# SparkFun_ProMicro_RP2350.net
KiCad netlist of a schematic drawn in EAGLE
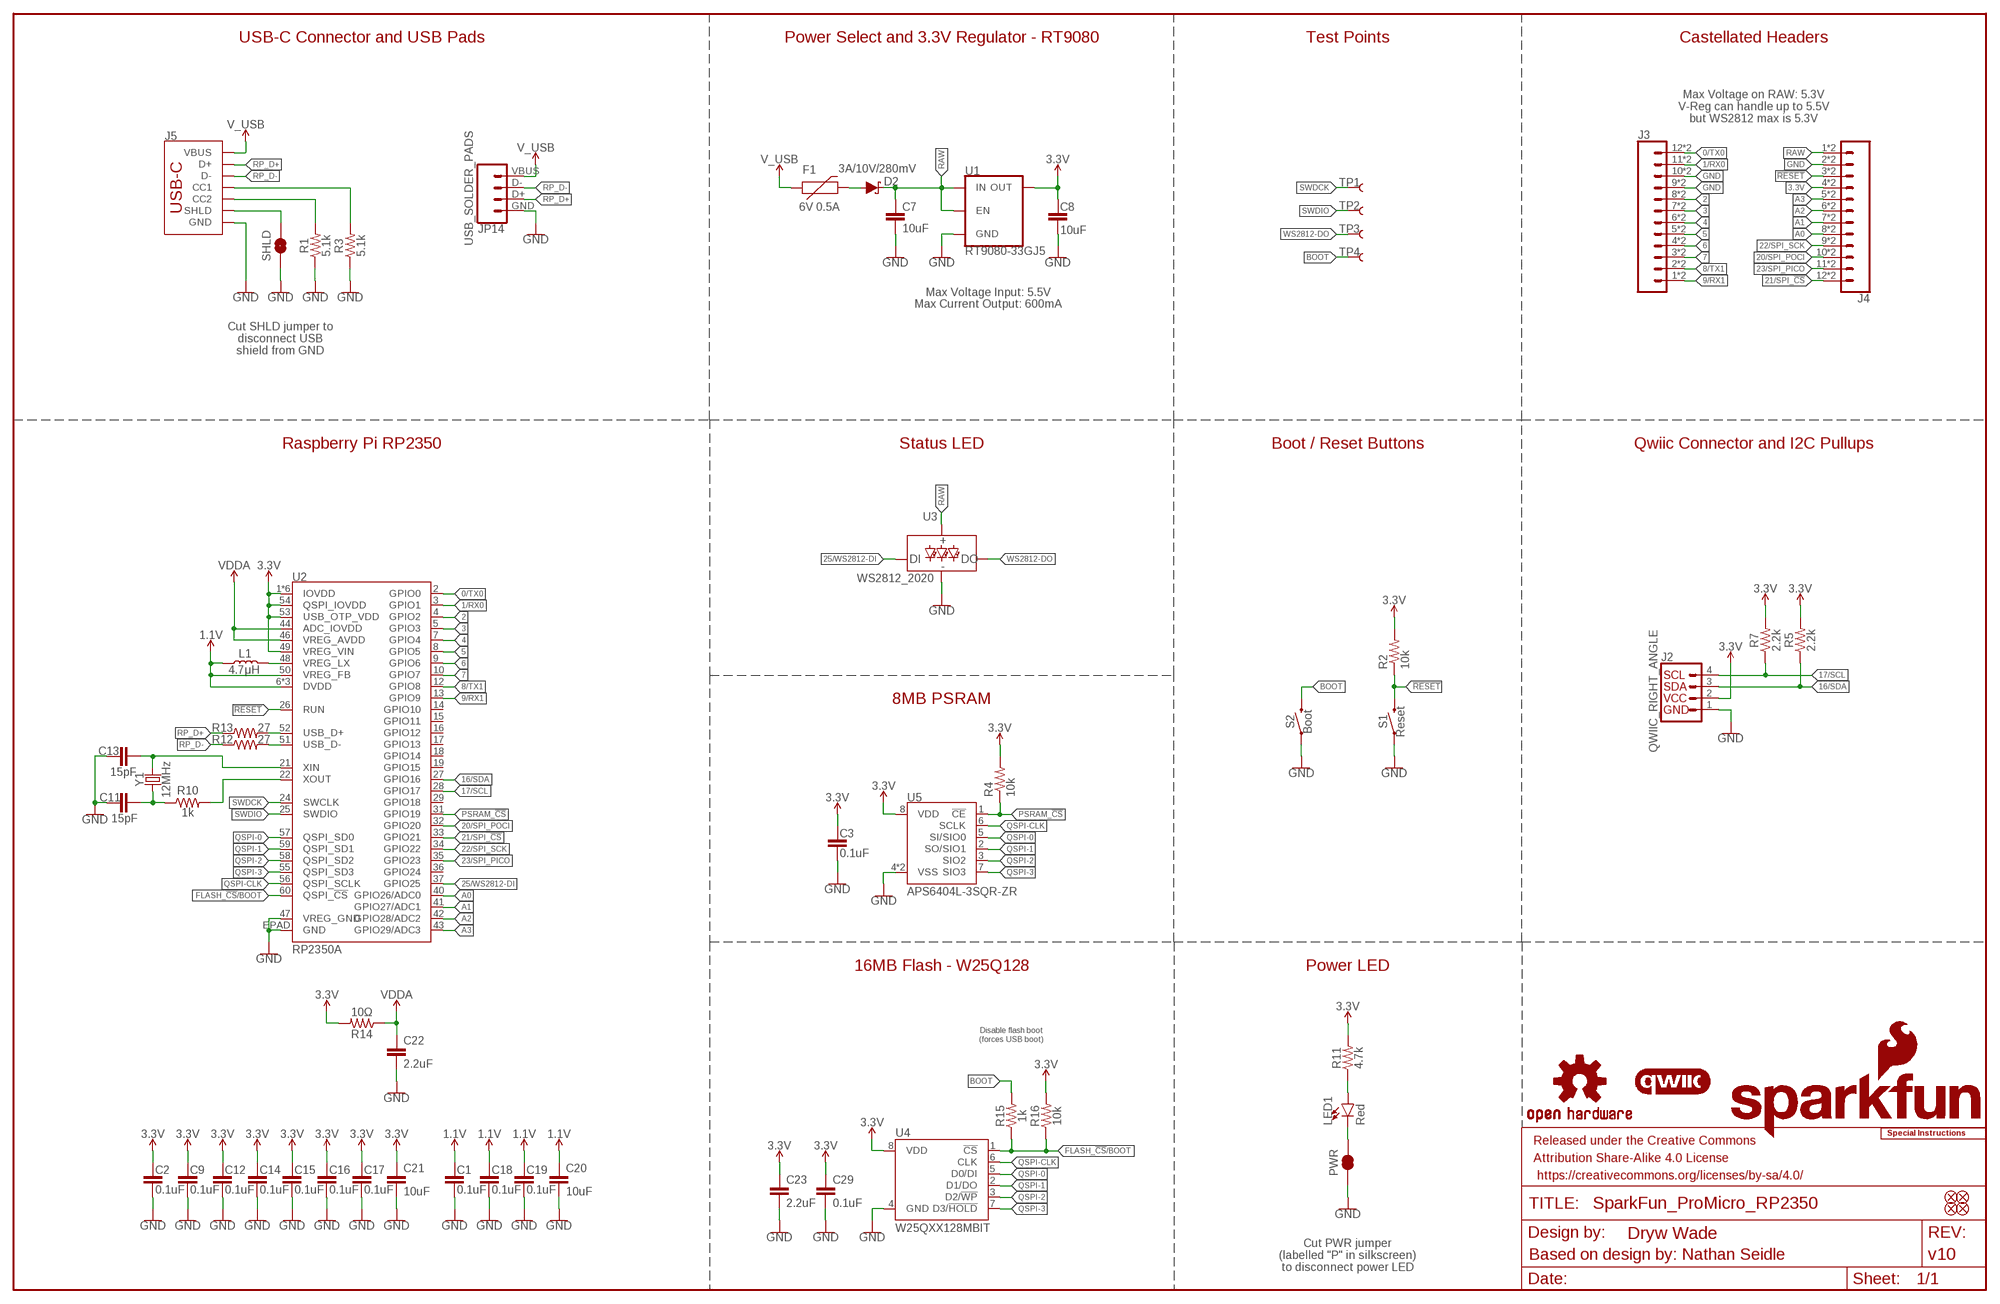
[diagram p0: schematic, sheet 1]

(export (version "E")
  (design (tool "Eeschema 10.0.6"))
  (components
    (comp (ref "C1")
      (value "0.1uF")
      (footprint "eagle-import:0402-TIGHT")
      (libsource (lib "eagle-import") (part "0.1UF-0402T-6.3V-10%-X7R"))
    )
    (comp (ref "C2")
      (value "0.1uF")
      (footprint "eagle-import:0402-TIGHT")
      (libsource (lib "eagle-import") (part "0.1UF-0402T-6.3V-10%-X7R"))
    )
    (comp (ref "C3")
      (value "0.1uF")
      (footprint "eagle-import:0402-TIGHT")
      (libsource (lib "eagle-import") (part "0.1UF-0402T-6.3V-10%-X7R"))
    )
    (comp (ref "C7")
      (value "10uF")
      (footprint "eagle-import:0402-TIGHT")
      (libsource (lib "eagle-import") (part "10UF-0402T-6.3V-20%"))
    )
    (comp (ref "C8")
      (value "10uF")
      (footprint "eagle-import:0402-TIGHT")
      (libsource (lib "eagle-import") (part "10UF-0402T-6.3V-20%"))
    )
    (comp (ref "C9")
      (value "0.1uF")
      (footprint "eagle-import:0402-TIGHT")
      (libsource (lib "eagle-import") (part "0.1UF-0402T-6.3V-10%-X7R"))
    )
    (comp (ref "C11")
      (value "15pF")
      (footprint "eagle-import:0402-TIGHT")
      (libsource (lib "eagle-import") (part "15PF-0402T-50V-5%"))
    )
    (comp (ref "C12")
      (value "0.1uF")
      (footprint "eagle-import:0402-TIGHT")
      (libsource (lib "eagle-import") (part "0.1UF-0402T-6.3V-10%-X7R"))
    )
    (comp (ref "C13")
      (value "15pF")
      (footprint "eagle-import:0402-TIGHT")
      (libsource (lib "eagle-import") (part "15PF-0402T-50V-5%"))
    )
    (comp (ref "C14")
      (value "0.1uF")
      (footprint "eagle-import:0402-TIGHT")
      (libsource (lib "eagle-import") (part "0.1UF-0402T-6.3V-10%-X7R"))
    )
    (comp (ref "C15")
      (value "0.1uF")
      (footprint "eagle-import:0402-TIGHT")
      (libsource (lib "eagle-import") (part "0.1UF-0402T-6.3V-10%-X7R"))
    )
    (comp (ref "C16")
      (value "0.1uF")
      (footprint "eagle-import:0402-TIGHT")
      (libsource (lib "eagle-import") (part "0.1UF-0402T-6.3V-10%-X7R"))
    )
    (comp (ref "C17")
      (value "0.1uF")
      (footprint "eagle-import:0402-TIGHT")
      (libsource (lib "eagle-import") (part "0.1UF-0402T-6.3V-10%-X7R"))
    )
    (comp (ref "C18")
      (value "0.1uF")
      (footprint "eagle-import:0402-TIGHT")
      (libsource (lib "eagle-import") (part "0.1UF-0402T-6.3V-10%-X7R"))
    )
    (comp (ref "C19")
      (value "0.1uF")
      (footprint "eagle-import:0402-TIGHT")
      (libsource (lib "eagle-import") (part "0.1UF-0402T-6.3V-10%-X7R"))
    )
    (comp (ref "C20")
      (value "10uF")
      (footprint "eagle-import:0402-TIGHT")
      (libsource (lib "eagle-import") (part "10UF-0402T-6.3V-20%"))
    )
    (comp (ref "C21")
      (value "10uF")
      (footprint "eagle-import:0402-TIGHT")
      (libsource (lib "eagle-import") (part "10UF-0402T-6.3V-20%"))
    )
    (comp (ref "C22")
      (value "2.2uF")
      (footprint "eagle-import:0402-TIGHT")
      (libsource (lib "eagle-import") (part "2.2UF-0402_TIGHT-10V-10%-X5R"))
    )
    (comp (ref "C23")
      (value "2.2uF")
      (footprint "eagle-import:0402-TIGHT")
      (libsource (lib "eagle-import") (part "2.2UF-0402_TIGHT-10V-10%-X5R"))
    )
    (comp (ref "C29")
      (value "0.1uF")
      (footprint "eagle-import:0402-TIGHT")
      (libsource (lib "eagle-import") (part "0.1UF-0402T-6.3V-10%-X7R"))
    )
    (comp (ref "D2")
      (value "3A/10V/280mV")
      (footprint "eagle-import:SOD-323")
      (libsource (lib "eagle-import") (part "DIODE-SCHOTTKY-BAT60A"))
    )
    (comp (ref "F1")
      (value "6V 0.5A")
      (footprint "eagle-import:0805")
      (libsource (lib "eagle-import") (part "PPTC_6V500MA"))
    )
    (comp (ref "FRAME2")
      (value "FRAME-LEDGER")
      (footprint "eagle-import:CREATIVE_COMMONS")
      (fields (field (name "DESIGNER") "Dryw Wade") (field (name "REV") "v10"))
      (libsource (lib "eagle-import") (part "FRAME-LEDGER"))
    )
    (comp (ref "J2")
      (value "QWIIC_RIGHT_ANGLE")
      (footprint "eagle-import:JST04_1MM_RA")
      (libsource (lib "eagle-import") (part "QWIIC_CONNECTORJS-1MM"))
    )
    (comp (ref "J3")
      (value "CONN_12CASTELLATED")
      (footprint "eagle-import:1X12_CASTELLATED")
      (libsource (lib "eagle-import") (part "CONN_12CASTELLATED"))
    )
    (comp (ref "J4")
      (value "CONN_12CASTELLATED")
      (footprint "eagle-import:1X12_CASTELLATED")
      (libsource (lib "eagle-import") (part "CONN_12CASTELLATED"))
    )
    (comp (ref "J5")
      (value "USB Female Type C Connector")
      (footprint "eagle-import:USB-C-16P_4LAYER-PADS")
      (libsource (lib "eagle-import") (part "USB_C_4-LAYER_PADS"))
    )
    (comp (ref "JP1")
      (value "FIDUCIAL1X2")
      (footprint "eagle-import:FIDUCIAL-1X2")
      (libsource (lib "eagle-import") (part "FIDUCIAL1X2"))
    )
    (comp (ref "JP2")
      (value "FIDUCIAL1X2")
      (footprint "eagle-import:FIDUCIAL-1X2")
      (libsource (lib "eagle-import") (part "FIDUCIAL1X2"))
    )
    (comp (ref "JP3")
      (value "FIDUCIAL1X2")
      (footprint "eagle-import:FIDUCIAL-1X2")
      (libsource (lib "eagle-import") (part "FIDUCIAL1X2"))
    )
    (comp (ref "JP4")
      (value "FIDUCIAL1X2")
      (footprint "eagle-import:FIDUCIAL-1X2")
      (libsource (lib "eagle-import") (part "FIDUCIAL1X2"))
    )
    (comp (ref "JP14")
      (value "USB_SOLDER_PADS")
      (footprint "eagle-import:USB-SOLDER-PADS")
      (libsource (lib "eagle-import") (part "USB_SOLDER_PADS"))
    )
    (comp (ref "L1")
      (value "4.7μH")
      (footprint "eagle-import:1008(2520)")
      (libsource (lib "eagle-import") (part "4.7μH_SHIELDED_INDUCTOR"))
    )
    (comp (ref "LED1")
      (value "Red")
      (footprint "eagle-import:LED-0603")
      (libsource (lib "eagle-import") (part "LED-RED_0603-KB"))
    )
    (comp (ref "LOGO1")
      (value "SFE_LOGO_NAME_FLAME.1_INCH")
      (footprint "eagle-import:SFE_LOGO_NAME_FLAME_.1")
      (libsource (lib "eagle-import") (part "SFE_LOGO_NAME_FLAME.1_INCH"))
    )
    (comp (ref "LOGO3")
      (value "QWIIC_LOGO_6MM")
      (footprint "eagle-import:QWIIC_6MM")
      (libsource (lib "eagle-import") (part "QWIIC_LOGO_6MM"))
    )
    (comp (ref "LOGO4")
      (value "SFE_LOGO_FLAME.1_INCH")
      (footprint "eagle-import:SFE_LOGO_FLAME_.1")
      (libsource (lib "eagle-import") (part "SFE_LOGO_FLAME.1_INCH"))
    )
    (comp (ref "LOGO5")
      (value "SPECIAL_INSTRUCTIONS-ORDERING")
      (footprint "eagle-import:ORDERING_INSTRUCTIONS")
      (libsource (lib "eagle-import") (part "SPECIAL_INSTRUCTIONS-ORDERING"))
    )
    (comp (ref "PWR")
      (value "JUMPER-SMT_2_NC_TRACE_SILK")
      (footprint "eagle-import:SMT-JUMPER_2_NC_TRACE_SILK")
      (libsource (lib "eagle-import") (part "JUMPER-SMT_2_NC_TRACE_SILK"))
    )
    (comp (ref "R1")
      (value "5.1k")
      (footprint "eagle-import:0402-TIGHT")
      (libsource (lib "eagle-import") (part "5.1KOHM-0402T-1/16W-1%"))
    )
    (comp (ref "R2")
      (value "10k")
      (footprint "eagle-import:0402-TIGHT")
      (libsource (lib "eagle-import") (part "10KOHM-0402T-1/16W-1%"))
    )
    (comp (ref "R3")
      (value "5.1k")
      (footprint "eagle-import:0402-TIGHT")
      (libsource (lib "eagle-import") (part "5.1KOHM-0402T-1/16W-1%"))
    )
    (comp (ref "R4")
      (value "10k")
      (footprint "eagle-import:0402-TIGHT")
      (libsource (lib "eagle-import") (part "10KOHM-0402T-1/16W-1%"))
    )
    (comp (ref "R5")
      (value "2.2k")
      (footprint "eagle-import:0402-TIGHT")
      (libsource (lib "eagle-import") (part "2.2KOHM-0402T-1/16W-1%"))
    )
    (comp (ref "R7")
      (value "2.2k")
      (footprint "eagle-import:0402-TIGHT")
      (libsource (lib "eagle-import") (part "2.2KOHM-0402T-1/16W-1%"))
    )
    (comp (ref "R10")
      (value "1k")
      (footprint "eagle-import:0402-TIGHT")
      (libsource (lib "eagle-import") (part "1KOHM-0402T-1/16W-1%"))
    )
    (comp (ref "R11")
      (value "4.7k")
      (footprint "eagle-import:0402-TIGHT")
      (libsource (lib "eagle-import") (part "4.7KOHM-0402T-1/16W-1%"))
    )
    (comp (ref "R12")
      (value "27")
      (footprint "eagle-import:0402-TIGHT")
      (libsource (lib "eagle-import") (part "27OHM"))
    )
    (comp (ref "R13")
      (value "27")
      (footprint "eagle-import:0402-TIGHT")
      (libsource (lib "eagle-import") (part "27OHM"))
    )
    (comp (ref "R14")
      (value "10Ω")
      (footprint "eagle-import:0402-TIGHT")
      (libsource (lib "eagle-import") (part "10OHM-0402-1/16W-5%"))
    )
    (comp (ref "R15")
      (value "1k")
      (footprint "eagle-import:0402-TIGHT")
      (libsource (lib "eagle-import") (part "1KOHM-0402T-1/16W-1%"))
    )
    (comp (ref "R16")
      (value "10k")
      (footprint "eagle-import:0402-TIGHT")
      (libsource (lib "eagle-import") (part "10KOHM-0402T-1/16W-1%"))
    )
    (comp (ref "S1")
      (value "Reset")
      (footprint "eagle-import:TACTILE_SWITCH_SMD_4.6X2.8MM")
      (libsource (lib "eagle-import") (part "MOMENTARY-SWITCH-SPST-SMD-4.6X2.8MM"))
    )
    (comp (ref "S2")
      (value "Boot")
      (footprint "eagle-import:TACTILE_SWITCH_SMD_4.6X2.8MM")
      (libsource (lib "eagle-import") (part "MOMENTARY-SWITCH-SPST-SMD-4.6X2.8MM"))
    )
    (comp (ref "SHLD")
      (value "JUMPER-SMT_2_NC_TRACE_SILK")
      (footprint "eagle-import:SMT-JUMPER_2_NC_TRACE_SILK")
      (libsource (lib "eagle-import") (part "JUMPER-SMT_2_NC_TRACE_SILK"))
    )
    (comp (ref "TP1")
      (value "TEST-POINT3X5")
      (footprint "eagle-import:PAD.03X.05")
      (libsource (lib "eagle-import") (part "TEST-POINT3X5"))
    )
    (comp (ref "TP2")
      (value "TEST-POINT3X5")
      (footprint "eagle-import:PAD.03X.05")
      (libsource (lib "eagle-import") (part "TEST-POINT3X5"))
    )
    (comp (ref "TP3")
      (value "TEST-POINT3X5")
      (footprint "eagle-import:PAD.03X.05")
      (libsource (lib "eagle-import") (part "TEST-POINT3X5"))
    )
    (comp (ref "TP4")
      (value "TEST-POINT3X5")
      (footprint "eagle-import:PAD.03X.05")
      (libsource (lib "eagle-import") (part "TEST-POINT3X5"))
    )
    (comp (ref "U$3")
      (value "OSHW-LOGOMINI")
      (footprint "eagle-import:OSHW-LOGO-MINI")
      (libsource (lib "eagle-import") (part "OSHW-LOGOMINI"))
    )
    (comp (ref "U1")
      (value "RT9080-33GJ5")
      (footprint "eagle-import:SOT23-5")
      (libsource (lib "eagle-import") (part "V_REG_RT9080-33GJ5"))
    )
    (comp (ref "U2")
      (value "RP2350A")
      (footprint "eagle-import:RP2350A")
      (libsource (lib "eagle-import") (part "RP2350A"))
    )
    (comp (ref "U3")
      (value "WS2812_2020")
      (footprint "eagle-import:WS2812-2020")
      (libsource (lib "eagle-import") (part "WS2812_2020"))
    )
    (comp (ref "U4")
      (value "W25QXX128MBIT")
      (footprint "eagle-import:WSON-8-6X5-SKINNY_CENTERPAD")
      (libsource (lib "eagle-import") (part "W25QXX128MBIT-6X5-SKINNY_CENTER"))
    )
    (comp (ref "U5")
      (value "APS6404L-3SQR-ZR")
      (footprint "eagle-import:APS6404L-3SQR-ZR")
      (libsource (lib "eagle-import") (part "APS6404L-3SQR-ZR"))
    )
    (comp (ref "Y1")
      (value "12MHz")
      (footprint "eagle-import:CRYSTAL-SMD-2X2.5MM")
      (libsource (lib "eagle-import") (part "CRYSTAL-12MHZ"))
    )
  )
  (nets
    (net (code "1") (name "/21{slash}SPI_~{CS}") (class "Default")
      (node (ref "J4") (pin "12") (pinfunction "12_12") (pintype "passive"))
      (node (ref "J4") (pin "12B") (pinfunction "12_12B") (pintype "passive"))
      (node (ref "U2") (pin "33") (pinfunction "GPIO21_33") (pintype "bidirectional"))
    )
    (net (code "2") (name "/FLASH_~{CS}{slash}BOOT") (class "Default")
      (node (ref "R15") (pin "1") (pinfunction "1_1") (pintype "passive"))
      (node (ref "R16") (pin "1") (pinfunction "1_1") (pintype "passive"))
      (node (ref "U2") (pin "60") (pinfunction "QSPI_~{CS}_60") (pintype "bidirectional"))
      (node (ref "U4") (pin "1") (pinfunction "~{CS}_1") (pintype "bidirectional"))
    )
    (net (code "3") (name "/PSRAM_~{CS}") (class "Default")
      (node (ref "R4") (pin "1") (pinfunction "1_1") (pintype "passive"))
      (node (ref "U2") (pin "31") (pinfunction "GPIO19_31") (pintype "bidirectional"))
      (node (ref "U5") (pin "1") (pinfunction "~{CE}_1") (pintype "bidirectional"))
    )
    (net (code "4") (name "/~{RESET}") (class "Default")
      (node (ref "J4") (pin "3") (pinfunction "3_3") (pintype "passive"))
      (node (ref "J4") (pin "3B") (pinfunction "3_3B") (pintype "passive"))
      (node (ref "R2") (pin "1") (pinfunction "1_1") (pintype "passive"))
      (node (ref "S1") (pin "3") (pinfunction "2_3") (pintype "passive"))
      (node (ref "S1") (pin "4") (pinfunction "2_4") (pintype "passive"))
      (node (ref "U2") (pin "26") (pinfunction "RUN_26") (pintype "bidirectional"))
    )
    (net (code "5") (name "0{slash}TX0") (class "Default")
      (node (ref "J3") (pin "12") (pinfunction "12_12") (pintype "passive"))
      (node (ref "J3") (pin "12B") (pinfunction "12_12B") (pintype "passive"))
      (node (ref "U2") (pin "2") (pinfunction "GPIO0_2") (pintype "bidirectional"))
    )
    (net (code "6") (name "1.1V") (class "Default")
      (node (ref "C1") (pin "1") (pinfunction "1_1") (pintype "passive"))
      (node (ref "C18") (pin "1") (pinfunction "1_1") (pintype "passive"))
      (node (ref "C19") (pin "1") (pinfunction "1_1") (pintype "passive"))
      (node (ref "C20") (pin "1") (pinfunction "1_1") (pintype "passive"))
      (node (ref "L1") (pin "1") (pinfunction "1_1") (pintype "passive"))
      (node (ref "U2") (pin "23") (pinfunction "DVDD_23") (pintype "bidirectional"))
      (node (ref "U2") (pin "39") (pinfunction "DVDD_39") (pintype "bidirectional"))
      (node (ref "U2") (pin "50") (pinfunction "VREG_FB_50") (pintype "bidirectional"))
      (node (ref "U2") (pin "6") (pinfunction "DVDD_6") (pintype "bidirectional"))
    )
    (net (code "7") (name "1{slash}RX0") (class "Default")
      (node (ref "J3") (pin "11") (pinfunction "11_11") (pintype "passive"))
      (node (ref "J3") (pin "11B") (pinfunction "11_11B") (pintype "passive"))
      (node (ref "U2") (pin "3") (pinfunction "GPIO1_3") (pintype "bidirectional"))
    )
    (net (code "8") (name "2") (class "Default")
      (node (ref "J3") (pin "8") (pinfunction "8_8") (pintype "passive"))
      (node (ref "J3") (pin "8B") (pinfunction "8_8B") (pintype "passive"))
      (node (ref "U2") (pin "4") (pinfunction "GPIO2_4") (pintype "bidirectional"))
    )
    (net (code "9") (name "3") (class "Default")
      (node (ref "J3") (pin "7") (pinfunction "7_7") (pintype "passive"))
      (node (ref "J3") (pin "7B") (pinfunction "7_7B") (pintype "passive"))
      (node (ref "U2") (pin "5") (pinfunction "GPIO3_5") (pintype "bidirectional"))
    )
    (net (code "10") (name "3.3V") (class "Default")
      (node (ref "C12") (pin "1") (pinfunction "1_1") (pintype "passive"))
      (node (ref "C14") (pin "1") (pinfunction "1_1") (pintype "passive"))
      (node (ref "C15") (pin "1") (pinfunction "1_1") (pintype "passive"))
      (node (ref "C16") (pin "1") (pinfunction "1_1") (pintype "passive"))
      (node (ref "C17") (pin "1") (pinfunction "1_1") (pintype "passive"))
      (node (ref "C2") (pin "1") (pinfunction "1_1") (pintype "passive"))
      (node (ref "C21") (pin "1") (pinfunction "1_1") (pintype "passive"))
      (node (ref "C23") (pin "1") (pinfunction "1_1") (pintype "passive"))
      (node (ref "C29") (pin "1") (pinfunction "1_1") (pintype "passive"))
      (node (ref "C3") (pin "1") (pinfunction "1_1") (pintype "passive"))
      (node (ref "C8") (pin "2") (pinfunction "2_2") (pintype "passive"))
      (node (ref "C9") (pin "1") (pinfunction "1_1") (pintype "passive"))
      (node (ref "J2") (pin "2") (pinfunction "2_2") (pintype "power_in"))
      (node (ref "J4") (pin "4") (pinfunction "4_4") (pintype "passive"))
      (node (ref "J4") (pin "4B") (pinfunction "4_4B") (pintype "passive"))
      (node (ref "R11") (pin "2") (pinfunction "2_2") (pintype "passive"))
      (node (ref "R14") (pin "2") (pinfunction "2_2") (pintype "passive"))
      (node (ref "R16") (pin "2") (pinfunction "2_2") (pintype "passive"))
      (node (ref "R2") (pin "2") (pinfunction "2_2") (pintype "passive"))
      (node (ref "R4") (pin "2") (pinfunction "2_2") (pintype "passive"))
      (node (ref "R5") (pin "2") (pinfunction "2_2") (pintype "passive"))
      (node (ref "R7") (pin "2") (pinfunction "2_2") (pintype "passive"))
      (node (ref "U1") (pin "5") (pinfunction "OUT_5") (pintype "passive"))
      (node (ref "U2") (pin "1") (pinfunction "IOVDD_1") (pintype "bidirectional"))
      (node (ref "U2") (pin "11") (pinfunction "IOVDD_11") (pintype "bidirectional"))
      (node (ref "U2") (pin "20") (pinfunction "IOVDD_20") (pintype "bidirectional"))
      (node (ref "U2") (pin "30") (pinfunction "IOVDD_30") (pintype "bidirectional"))
      (node (ref "U2") (pin "38") (pinfunction "IOVDD_38") (pintype "bidirectional"))
      (node (ref "U2") (pin "45") (pinfunction "IOVDD_45") (pintype "bidirectional"))
      (node (ref "U2") (pin "49") (pinfunction "VREG_VIN_49") (pintype "bidirectional"))
      (node (ref "U2") (pin "53") (pinfunction "USB_OTP_VDD_53") (pintype "bidirectional"))
      (node (ref "U2") (pin "54") (pinfunction "QSPI_IOVDD_54") (pintype "bidirectional"))
      (node (ref "U4") (pin "8") (pinfunction "VDD_8") (pintype "bidirectional"))
      (node (ref "U5") (pin "8") (pinfunction "VDD_8") (pintype "bidirectional"))
    )
    (net (code "11") (name "4") (class "Default")
      (node (ref "J3") (pin "6") (pinfunction "6_6") (pintype "passive"))
      (node (ref "J3") (pin "6B") (pinfunction "6_6B") (pintype "passive"))
      (node (ref "U2") (pin "7") (pinfunction "GPIO4_7") (pintype "bidirectional"))
    )
    (net (code "12") (name "5") (class "Default")
      (node (ref "J3") (pin "5") (pinfunction "5_5") (pintype "passive"))
      (node (ref "J3") (pin "5B") (pinfunction "5_5B") (pintype "passive"))
      (node (ref "U2") (pin "8") (pinfunction "GPIO5_8") (pintype "bidirectional"))
    )
    (net (code "13") (name "6") (class "Default")
      (node (ref "J3") (pin "4") (pinfunction "4_4") (pintype "passive"))
      (node (ref "J3") (pin "4B") (pinfunction "4_4B") (pintype "passive"))
      (node (ref "U2") (pin "9") (pinfunction "GPIO6_9") (pintype "bidirectional"))
    )
    (net (code "14") (name "7") (class "Default")
      (node (ref "J3") (pin "3") (pinfunction "3_3") (pintype "passive"))
      (node (ref "J3") (pin "3B") (pinfunction "3_3B") (pintype "passive"))
      (node (ref "U2") (pin "10") (pinfunction "GPIO7_10") (pintype "bidirectional"))
    )
    (net (code "15") (name "8{slash}TX1") (class "Default")
      (node (ref "J3") (pin "2") (pinfunction "2_2") (pintype "passive"))
      (node (ref "J3") (pin "2B") (pinfunction "2_2B") (pintype "passive"))
      (node (ref "U2") (pin "12") (pinfunction "GPIO8_12") (pintype "bidirectional"))
    )
    (net (code "16") (name "9{slash}RX1") (class "Default")
      (node (ref "J3") (pin "1") (pinfunction "1_1") (pintype "passive"))
      (node (ref "J3") (pin "1B") (pinfunction "1_1B") (pintype "passive"))
      (node (ref "U2") (pin "13") (pinfunction "GPIO9_13") (pintype "bidirectional"))
    )
    (net (code "17") (name "16{slash}SDA") (class "Default")
      (node (ref "J2") (pin "3") (pinfunction "3_3") (pintype "passive"))
      (node (ref "R5") (pin "1") (pinfunction "1_1") (pintype "passive"))
      (node (ref "U2") (pin "27") (pinfunction "GPIO16_27") (pintype "bidirectional"))
    )
    (net (code "18") (name "17{slash}SCL") (class "Default")
      (node (ref "J2") (pin "4") (pinfunction "4_4") (pintype "passive"))
      (node (ref "R7") (pin "1") (pinfunction "1_1") (pintype "passive"))
      (node (ref "U2") (pin "28") (pinfunction "GPIO17_28") (pintype "bidirectional"))
    )
    (net (code "19") (name "20{slash}SPI_POCI") (class "Default")
      (node (ref "J4") (pin "10") (pinfunction "10_10") (pintype "passive"))
      (node (ref "J4") (pin "10B") (pinfunction "10_10B") (pintype "passive"))
      (node (ref "U2") (pin "32") (pinfunction "GPIO20_32") (pintype "bidirectional"))
    )
    (net (code "20") (name "22{slash}SPI_SCK") (class "Default")
      (node (ref "J4") (pin "9") (pinfunction "9_9") (pintype "passive"))
      (node (ref "J4") (pin "9B") (pinfunction "9_9B") (pintype "passive"))
      (node (ref "U2") (pin "34") (pinfunction "GPIO22_34") (pintype "bidirectional"))
    )
    (net (code "21") (name "23{slash}SPI_PICO") (class "Default")
      (node (ref "J4") (pin "11") (pinfunction "11_11") (pintype "passive"))
      (node (ref "J4") (pin "11B") (pinfunction "11_11B") (pintype "passive"))
      (node (ref "U2") (pin "35") (pinfunction "GPIO23_35") (pintype "bidirectional"))
    )
    (net (code "22") (name "25{slash}WS2812-DI") (class "Default")
      (node (ref "U2") (pin "37") (pinfunction "GPIO25_37") (pintype "bidirectional"))
      (node (ref "U3") (pin "DI") (pinfunction "DI_DI") (pintype "bidirectional"))
    )
    (net (code "23") (name "A0") (class "Default")
      (node (ref "J4") (pin "8") (pinfunction "8_8") (pintype "passive"))
      (node (ref "J4") (pin "8B") (pinfunction "8_8B") (pintype "passive"))
      (node (ref "U2") (pin "40") (pinfunction "GPIO26/ADC0_40") (pintype "bidirectional"))
    )
    (net (code "24") (name "A1") (class "Default")
      (node (ref "J4") (pin "7") (pinfunction "7_7") (pintype "passive"))
      (node (ref "J4") (pin "7B") (pinfunction "7_7B") (pintype "passive"))
      (node (ref "U2") (pin "41") (pinfunction "GPIO27/ADC1_41") (pintype "bidirectional"))
    )
    (net (code "25") (name "A2") (class "Default")
      (node (ref "J4") (pin "6") (pinfunction "6_6") (pintype "passive"))
      (node (ref "J4") (pin "6B") (pinfunction "6_6B") (pintype "passive"))
      (node (ref "U2") (pin "42") (pinfunction "GPIO28/ADC2_42") (pintype "bidirectional"))
    )
    (net (code "26") (name "A3") (class "Default")
      (node (ref "J4") (pin "5") (pinfunction "5_5") (pintype "passive"))
      (node (ref "J4") (pin "5B") (pinfunction "5_5B") (pintype "passive"))
      (node (ref "U2") (pin "43") (pinfunction "GPIO29/ADC3_43") (pintype "bidirectional"))
    )
    (net (code "27") (name "BOOT") (class "Default")
      (node (ref "R15") (pin "2") (pinfunction "2_2") (pintype "passive"))
      (node (ref "S2") (pin "3") (pinfunction "2_3") (pintype "passive"))
      (node (ref "S2") (pin "4") (pinfunction "2_4") (pintype "passive"))
      (node (ref "TP4") (pin "1") (pinfunction "1_1") (pintype "bidirectional"))
    )
    (net (code "28") (name "GND") (class "Default")
      (node (ref "C1") (pin "2") (pinfunction "2_2") (pintype "passive"))
      (node (ref "C11") (pin "1") (pinfunction "1_1") (pintype "passive"))
      (node (ref "C12") (pin "2") (pinfunction "2_2") (pintype "passive"))
      (node (ref "C13") (pin "1") (pinfunction "1_1") (pintype "passive"))
      (node (ref "C14") (pin "2") (pinfunction "2_2") (pintype "passive"))
      (node (ref "C15") (pin "2") (pinfunction "2_2") (pintype "passive"))
      (node (ref "C16") (pin "2") (pinfunction "2_2") (pintype "passive"))
      (node (ref "C17") (pin "2") (pinfunction "2_2") (pintype "passive"))
      (node (ref "C18") (pin "2") (pinfunction "2_2") (pintype "passive"))
      (node (ref "C19") (pin "2") (pinfunction "2_2") (pintype "passive"))
      (node (ref "C2") (pin "2") (pinfunction "2_2") (pintype "passive"))
      (node (ref "C20") (pin "2") (pinfunction "2_2") (pintype "passive"))
      (node (ref "C21") (pin "2") (pinfunction "2_2") (pintype "passive"))
      (node (ref "C22") (pin "2") (pinfunction "2_2") (pintype "passive"))
      (node (ref "C23") (pin "2") (pinfunction "2_2") (pintype "passive"))
      (node (ref "C29") (pin "2") (pinfunction "2_2") (pintype "passive"))
      (node (ref "C3") (pin "2") (pinfunction "2_2") (pintype "passive"))
      (node (ref "C7") (pin "1") (pinfunction "1_1") (pintype "passive"))
      (node (ref "C8") (pin "1") (pinfunction "1_1") (pintype "passive"))
      (node (ref "C9") (pin "2") (pinfunction "2_2") (pintype "passive"))
      (node (ref "J2") (pin "1") (pinfunction "1_1") (pintype "power_in"))
      (node (ref "J3") (pin "10") (pinfunction "10_10") (pintype "passive"))
      (node (ref "J3") (pin "10B") (pinfunction "10_10B") (pintype "passive"))
      (node (ref "J3") (pin "9") (pinfunction "9_9") (pintype "passive"))
      (node (ref "J3") (pin "9B") (pinfunction "9_9B") (pintype "passive"))
      (node (ref "J4") (pin "2") (pinfunction "2_2") (pintype "passive"))
      (node (ref "J4") (pin "2B") (pinfunction "2_2B") (pintype "passive"))
      (node (ref "J5") (pin "GND") (pinfunction "GND_GND") (pintype "bidirectional"))
      (node (ref "J5") (pin "GND2") (pinfunction "GND_GND2") (pintype "bidirectional"))
      (node (ref "JP14") (pin "GND") (pinfunction "4_GND") (pintype "passive"))
      (node (ref "PWR") (pin "1") (pinfunction "1_1") (pintype "passive"))
      (node (ref "R1") (pin "1") (pinfunction "1_1") (pintype "passive"))
      (node (ref "R3") (pin "1") (pinfunction "1_1") (pintype "passive"))
      (node (ref "S1") (pin "1") (pinfunction "1_1") (pintype "passive"))
      (node (ref "S1") (pin "2") (pinfunction "1_2") (pintype "passive"))
      (node (ref "S2") (pin "1") (pinfunction "1_1") (pintype "passive"))
      (node (ref "S2") (pin "2") (pinfunction "1_2") (pintype "passive"))
      (node (ref "SHLD") (pin "2") (pinfunction "2_2") (pintype "passive"))
      (node (ref "U1") (pin "2") (pinfunction "GND_2") (pintype "input"))
      (node (ref "U2") (pin "47") (pinfunction "VREG_GND_47") (pintype "bidirectional"))
      (node (ref "U2") (pin "EPAD") (pinfunction "GND_EPAD") (pintype "bidirectional"))
      (node (ref "U3") (pin "GND") (pinfunction "GND_GND") (pintype "bidirectional"))
      (node (ref "U4") (pin "4") (pinfunction "GND_4") (pintype "bidirectional"))
      (node (ref "U5") (pin "4") (pinfunction "VSS_4") (pintype "bidirectional"))
      (node (ref "U5") (pin "9") (pinfunction "VSS_9") (pintype "bidirectional"))
    )
    (net (code "29") (name "Net-(D2-PadA)") (class "Default")
      (node (ref "D2") (pin "A") (pinfunction "A_A") (pintype "passive"))
      (node (ref "F1") (pin "2") (pinfunction "2_2") (pintype "bidirectional"))
    )
    (net (code "30") (name "Net-(J5-CC1)") (class "Default")
      (node (ref "J5") (pin "A5") (pinfunction "CC1_A5") (pintype "bidirectional"))
      (node (ref "R3") (pin "2") (pinfunction "2_2") (pintype "passive"))
    )
    (net (code "31") (name "Net-(J5-CC2)") (class "Default")
      (node (ref "J5") (pin "B5") (pinfunction "CC2_B5") (pintype "bidirectional"))
      (node (ref "R1") (pin "2") (pinfunction "2_2") (pintype "passive"))
    )
    (net (code "32") (name "Net-(J5-SHLD-PadSHLD1)") (class "Default")
      (node (ref "J5") (pin "SHLD1") (pinfunction "SHLD_SHLD1") (pintype "bidirectional"))
      (node (ref "J5") (pin "SHLD2") (pinfunction "SHLD_SHLD2") (pintype "bidirectional"))
      (node (ref "J5") (pin "SHLD3") (pinfunction "SHLD_SHLD3") (pintype "bidirectional"))
      (node (ref "J5") (pin "SHLD4") (pinfunction "SHLD_SHLD4") (pintype "bidirectional"))
      (node (ref "SHLD") (pin "1") (pinfunction "1_1") (pintype "passive"))
    )
    (net (code "33") (name "Net-(LED1-PadA)") (class "Default")
      (node (ref "LED1") (pin "A") (pinfunction "A_A") (pintype "passive"))
      (node (ref "R11") (pin "1") (pinfunction "1_1") (pintype "passive"))
    )
    (net (code "34") (name "Net-(LED1-PadC)") (class "Default")
      (node (ref "LED1") (pin "C") (pinfunction "C_C") (pintype "passive"))
      (node (ref "PWR") (pin "2") (pinfunction "2_2") (pintype "passive"))
    )
    (net (code "35") (name "Net-(U2-USB_D+)") (class "Default")
      (node (ref "R13") (pin "2") (pinfunction "2_2") (pintype "passive"))
      (node (ref "U2") (pin "52") (pinfunction "USB_D+_52") (pintype "bidirectional"))
    )
    (net (code "36") (name "Net-(U2-USB_D-)") (class "Default")
      (node (ref "R12") (pin "2") (pinfunction "2_2") (pintype "passive"))
      (node (ref "U2") (pin "51") (pinfunction "USB_D-_51") (pintype "bidirectional"))
    )
    (net (code "37") (name "Net-(U2-VREG_LX)") (class "Default")
      (node (ref "L1") (pin "2") (pinfunction "2_2") (pintype "passive"))
      (node (ref "U2") (pin "48") (pinfunction "VREG_LX_48") (pintype "bidirectional"))
    )
    (net (code "38") (name "Net-(U2-XIN)") (class "Default")
      (node (ref "C13") (pin "2") (pinfunction "2_2") (pintype "passive"))
      (node (ref "U2") (pin "21") (pinfunction "XIN_21") (pintype "bidirectional"))
      (node (ref "Y1") (pin "P3") (pinfunction "2_P3") (pintype "passive"))
    )
    (net (code "39") (name "Net-(U2-XOUT)") (class "Default")
      (node (ref "R10") (pin "2") (pinfunction "2_2") (pintype "passive"))
      (node (ref "U2") (pin "22") (pinfunction "XOUT_22") (pintype "bidirectional"))
    )
    (net (code "40") (name "Net-(Y1-1)") (class "Default")
      (node (ref "C11") (pin "2") (pinfunction "2_2") (pintype "passive"))
      (node (ref "R10") (pin "1") (pinfunction "1_1") (pintype "passive"))
      (node (ref "Y1") (pin "P1") (pinfunction "1_P1") (pintype "passive"))
    )
    (net (code "41") (name "QSPI-0") (class "Default")
      (node (ref "U2") (pin "57") (pinfunction "QSPI_SD0_57") (pintype "bidirectional"))
      (node (ref "U4") (pin "5") (pinfunction "D0/DI_5") (pintype "bidirectional"))
      (node (ref "U5") (pin "5") (pinfunction "SI/SIO0_5") (pintype "bidirectional"))
    )
    (net (code "42") (name "QSPI-1") (class "Default")
      (node (ref "U2") (pin "59") (pinfunction "QSPI_SD1_59") (pintype "bidirectional"))
      (node (ref "U4") (pin "2") (pinfunction "D1/DO_2") (pintype "bidirectional"))
      (node (ref "U5") (pin "2") (pinfunction "SO/SIO1_2") (pintype "bidirectional"))
    )
    (net (code "43") (name "QSPI-2") (class "Default")
      (node (ref "U2") (pin "58") (pinfunction "QSPI_SD2_58") (pintype "bidirectional"))
      (node (ref "U4") (pin "3") (pinfunction "D2/~{WP}_3") (pintype "bidirectional"))
      (node (ref "U5") (pin "3") (pinfunction "SIO2_3") (pintype "bidirectional"))
    )
    (net (code "44") (name "QSPI-3") (class "Default")
      (node (ref "U2") (pin "55") (pinfunction "QSPI_SD3_55") (pintype "bidirectional"))
      (node (ref "U4") (pin "7") (pinfunction "D3/~{HOLD}_7") (pintype "bidirectional"))
      (node (ref "U5") (pin "7") (pinfunction "SIO3_7") (pintype "bidirectional"))
    )
    (net (code "45") (name "QSPI-CLK") (class "Default")
      (node (ref "U2") (pin "56") (pinfunction "QSPI_SCLK_56") (pintype "bidirectional"))
      (node (ref "U4") (pin "6") (pinfunction "CLK_6") (pintype "bidirectional"))
      (node (ref "U5") (pin "6") (pinfunction "SCLK_6") (pintype "bidirectional"))
    )
    (net (code "46") (name "RAW") (class "Default")
      (node (ref "C7") (pin "2") (pinfunction "2_2") (pintype "passive"))
      (node (ref "D2") (pin "C") (pinfunction "C_C") (pintype "passive"))
      (node (ref "J4") (pin "1") (pinfunction "1_1") (pintype "passive"))
      (node (ref "J4") (pin "1B") (pinfunction "1_1B") (pintype "passive"))
      (node (ref "U1") (pin "1") (pinfunction "IN_1") (pintype "input"))
      (node (ref "U1") (pin "3") (pinfunction "EN_3") (pintype "input"))
      (node (ref "U3") (pin "VCC") (pinfunction "VCC_VCC") (pintype "bidirectional"))
    )
    (net (code "47") (name "RP_D+") (class "Default")
      (node (ref "J5") (pin "A6") (pinfunction "D+_A6") (pintype "bidirectional"))
      (node (ref "J5") (pin "B6") (pinfunction "D+_B6") (pintype "bidirectional"))
      (node (ref "JP14") (pin "D+") (pinfunction "3_D+") (pintype "passive"))
      (node (ref "R13") (pin "1") (pinfunction "1_1") (pintype "passive"))
    )
    (net (code "48") (name "RP_D-") (class "Default")
      (node (ref "J5") (pin "A7") (pinfunction "D-_A7") (pintype "bidirectional"))
      (node (ref "J5") (pin "B7") (pinfunction "D-_B7") (pintype "bidirectional"))
      (node (ref "JP14") (pin "D-") (pinfunction "2_D-") (pintype "passive"))
      (node (ref "R12") (pin "1") (pinfunction "1_1") (pintype "passive"))
    )
    (net (code "49") (name "SWDCK") (class "Default")
      (node (ref "TP1") (pin "1") (pinfunction "1_1") (pintype "bidirectional"))
      (node (ref "U2") (pin "24") (pinfunction "SWCLK_24") (pintype "bidirectional"))
    )
    (net (code "50") (name "SWDIO") (class "Default")
      (node (ref "TP2") (pin "1") (pinfunction "1_1") (pintype "bidirectional"))
      (node (ref "U2") (pin "25") (pinfunction "SWDIO_25") (pintype "bidirectional"))
    )
    (net (code "51") (name "VDDA") (class "Default")
      (node (ref "C22") (pin "1") (pinfunction "1_1") (pintype "passive"))
      (node (ref "R14") (pin "1") (pinfunction "1_1") (pintype "passive"))
      (node (ref "U2") (pin "44") (pinfunction "ADC_IOVDD_44") (pintype "bidirectional"))
      (node (ref "U2") (pin "46") (pinfunction "VREG_AVDD_46") (pintype "bidirectional"))
    )
    (net (code "52") (name "V_USB") (class "Default")
      (node (ref "F1") (pin "1") (pinfunction "1_1") (pintype "bidirectional"))
      (node (ref "J5") (pin "VBUS1") (pinfunction "VBUS_VBUS1") (pintype "bidirectional"))
      (node (ref "J5") (pin "VBUS2") (pinfunction "VBUS_VBUS2") (pintype "bidirectional"))
      (node (ref "JP14") (pin "VBUS") (pinfunction "1_VBUS") (pintype "passive"))
    )
    (net (code "53") (name "WS2812-DO") (class "Default")
      (node (ref "TP3") (pin "1") (pinfunction "1_1") (pintype "bidirectional"))
      (node (ref "U3") (pin "DO") (pinfunction "DO_DO") (pintype "bidirectional"))
    )
    (net (code "54") (name "unconnected-(U2-GPIO10-Pad14)") (class "Default")
      (node (ref "U2") (pin "14") (pinfunction "GPIO10_14") (pintype "bidirectional"))
    )
    (net (code "55") (name "unconnected-(U2-GPIO11-Pad15)") (class "Default")
      (node (ref "U2") (pin "15") (pinfunction "GPIO11_15") (pintype "bidirectional"))
    )
    (net (code "56") (name "unconnected-(U2-GPIO12-Pad16)") (class "Default")
      (node (ref "U2") (pin "16") (pinfunction "GPIO12_16") (pintype "bidirectional"))
    )
    (net (code "57") (name "unconnected-(U2-GPIO13-Pad17)") (class "Default")
      (node (ref "U2") (pin "17") (pinfunction "GPIO13_17") (pintype "bidirectional"))
    )
    (net (code "58") (name "unconnected-(U2-GPIO14-Pad18)") (class "Default")
      (node (ref "U2") (pin "18") (pinfunction "GPIO14_18") (pintype "bidirectional"))
    )
    (net (code "59") (name "unconnected-(U2-GPIO15-Pad19)") (class "Default")
      (node (ref "U2") (pin "19") (pinfunction "GPIO15_19") (pintype "bidirectional"))
    )
    (net (code "60") (name "unconnected-(U2-GPIO18-Pad29)") (class "Default")
      (node (ref "U2") (pin "29") (pinfunction "GPIO18_29") (pintype "bidirectional"))
    )
    (net (code "61") (name "unconnected-(U2-GPIO24-Pad36)") (class "Default")
      (node (ref "U2") (pin "36") (pinfunction "GPIO24_36") (pintype "bidirectional"))
    )
  )
)
